# NonConformingThumbs.net
KiCad netlist of a schematic drawn in EAGLE
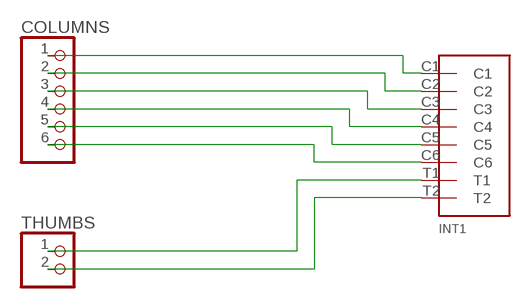
[diagram p0: schematic, sheet 1]

(export (version "E")
  (design (tool "Eeschema 10.0.6"))
  (components
    (comp (ref "COLUMNS")
      (value "PINHD-1X6")
      (footprint "eagle-import:1X06")
      (libsource (lib "eagle-import") (part "PINHD-1X6"))
    )
    (comp (ref "INT1")
      (value "INTRCNNT4X2")
      (footprint "eagle-import:INTRRIBBON")
      (libsource (lib "eagle-import") (part "INTRCNNT4X2"))
    )
    (comp (ref "THUMBS")
      (value "PINHD-1X2")
      (footprint "eagle-import:1X02")
      (libsource (lib "eagle-import") (part "PINHD-1X2"))
    )
  )
  (nets
    (net (code "1") (name "Net-(COLUMNS-Pad1)") (class "Default")
      (node (ref "COLUMNS") (pin "1") (pinfunction "1_1") (pintype "passive"))
      (node (ref "INT1") (pin "C1") (pinfunction "C1_C1") (pintype "bidirectional"))
    )
    (net (code "2") (name "Net-(COLUMNS-Pad2)") (class "Default")
      (node (ref "COLUMNS") (pin "2") (pinfunction "2_2") (pintype "passive"))
      (node (ref "INT1") (pin "C2") (pinfunction "C2_C2") (pintype "bidirectional"))
    )
    (net (code "3") (name "Net-(COLUMNS-Pad3)") (class "Default")
      (node (ref "COLUMNS") (pin "3") (pinfunction "3_3") (pintype "passive"))
      (node (ref "INT1") (pin "C3") (pinfunction "C3_C3") (pintype "bidirectional"))
    )
    (net (code "4") (name "Net-(COLUMNS-Pad4)") (class "Default")
      (node (ref "COLUMNS") (pin "4") (pinfunction "4_4") (pintype "passive"))
      (node (ref "INT1") (pin "C4") (pinfunction "C4_C4") (pintype "bidirectional"))
    )
    (net (code "5") (name "Net-(COLUMNS-Pad5)") (class "Default")
      (node (ref "COLUMNS") (pin "5") (pinfunction "5_5") (pintype "passive"))
      (node (ref "INT1") (pin "C5") (pinfunction "C5_C5") (pintype "bidirectional"))
    )
    (net (code "6") (name "Net-(COLUMNS-Pad6)") (class "Default")
      (node (ref "COLUMNS") (pin "6") (pinfunction "6_6") (pintype "passive"))
      (node (ref "INT1") (pin "C6") (pinfunction "C6_C6") (pintype "bidirectional"))
    )
    (net (code "7") (name "Net-(INT1-PadT1)") (class "Default")
      (node (ref "INT1") (pin "T1") (pinfunction "T1_T1") (pintype "bidirectional"))
      (node (ref "THUMBS") (pin "1") (pinfunction "1_1") (pintype "passive"))
    )
    (net (code "8") (name "Net-(INT1-PadT2)") (class "Default")
      (node (ref "INT1") (pin "T2") (pinfunction "T2_T2") (pintype "bidirectional"))
      (node (ref "THUMBS") (pin "2") (pinfunction "2_2") (pintype "passive"))
    )
  )
)
